# Board.net
KiCad netlist of a schematic drawn in Altium Designer
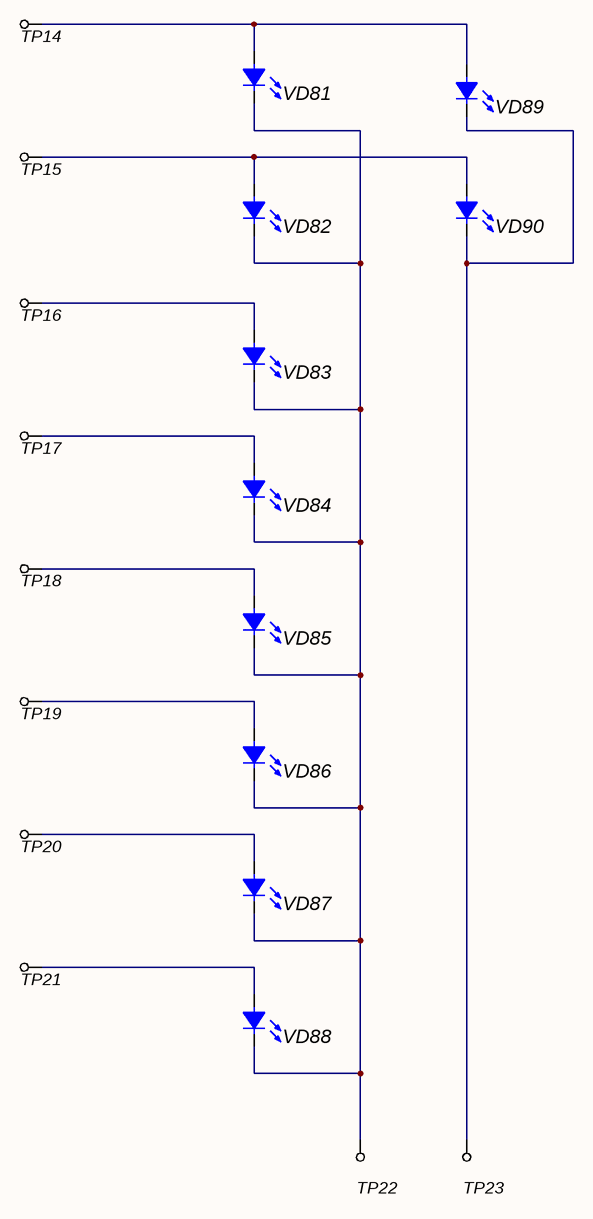
[diagram p0: Board.SchDoc]

(export (version "E")
  (design (tool "Eeschema 10.0.6"))
  (components
    (comp (ref "TP14")
      (value "Testpoint_HS1mm")
      (footprint "TestPoint(without 3D)")
      (libsource (lib "connector") (part "Testpoint_HS1mm"))
    )
    (comp (ref "TP15")
      (value "Testpoint_HS1mm")
      (footprint "TestPoint(without 3D)")
      (libsource (lib "connector") (part "Testpoint_HS1mm"))
    )
    (comp (ref "TP16")
      (value "Testpoint_HS1mm")
      (footprint "TestPoint(without 3D)")
      (libsource (lib "connector") (part "Testpoint_HS1mm"))
    )
    (comp (ref "TP17")
      (value "Testpoint_HS1mm")
      (footprint "TestPoint(without 3D)")
      (libsource (lib "connector") (part "Testpoint_HS1mm"))
    )
    (comp (ref "TP18")
      (value "Testpoint_HS1mm")
      (footprint "TestPoint(without 3D)")
      (libsource (lib "connector") (part "Testpoint_HS1mm"))
    )
    (comp (ref "TP19")
      (value "Testpoint_HS1mm")
      (footprint "TestPoint(without 3D)")
      (libsource (lib "connector") (part "Testpoint_HS1mm"))
    )
    (comp (ref "TP20")
      (value "Testpoint_HS1mm")
      (footprint "TestPoint(without 3D)")
      (libsource (lib "connector") (part "Testpoint_HS1mm"))
    )
    (comp (ref "TP21")
      (value "Testpoint_HS1mm")
      (footprint "TestPoint(without 3D)")
      (libsource (lib "connector") (part "Testpoint_HS1mm"))
    )
    (comp (ref "TP22")
      (value "Testpoint_HS1mm")
      (footprint "TestPoint(without 3D)")
      (libsource (lib "connector") (part "Testpoint_HS1mm"))
    )
    (comp (ref "TP23")
      (value "Testpoint_HS1mm")
      (footprint "TestPoint(without 3D)")
      (libsource (lib "connector") (part "Testpoint_HS1mm"))
    )
    (comp (ref "VD81")
      (value "~")
      (footprint "LED: 1206Y")
      (fields (field (name "VALUEMANUFACTURERPARTNUMBER") "LED, Green, *, *, *, -55...+150°C"))
      (libsource (lib "diode") (part "LED_single"))
    )
    (comp (ref "VD82")
      (value "~")
      (footprint "LED: 1206Y")
      (fields (field (name "VALUEMANUFACTURERPARTNUMBER") "LED, Green, *, *, *, -55...+150°C"))
      (libsource (lib "diode") (part "LED_single"))
    )
    (comp (ref "VD83")
      (value "~")
      (footprint "LED: 1206Y")
      (fields (field (name "VALUEMANUFACTURERPARTNUMBER") "LED, Green, *, *, *, -55...+150°C"))
      (libsource (lib "diode") (part "LED_single"))
    )
    (comp (ref "VD84")
      (value "~")
      (footprint "LED: 1206Y")
      (fields (field (name "VALUEMANUFACTURERPARTNUMBER") "LED, Green, *, *, *, -55...+150°C"))
      (libsource (lib "diode") (part "LED_single"))
    )
    (comp (ref "VD85")
      (value "~")
      (footprint "LED: 1206Y")
      (fields (field (name "VALUEMANUFACTURERPARTNUMBER") "LED, Green, *, *, *, -55...+150°C"))
      (libsource (lib "diode") (part "LED_single"))
    )
    (comp (ref "VD86")
      (value "~")
      (footprint "LED: 1206Y")
      (fields (field (name "VALUEMANUFACTURERPARTNUMBER") "LED, Green, *, *, *, -55...+150°C"))
      (libsource (lib "diode") (part "LED_single"))
    )
    (comp (ref "VD87")
      (value "~")
      (footprint "LED: 1206Y")
      (fields (field (name "VALUEMANUFACTURERPARTNUMBER") "LED, Green, *, *, *, -55...+150°C"))
      (libsource (lib "diode") (part "LED_single"))
    )
    (comp (ref "VD88")
      (value "~")
      (footprint "LED: 1206Y")
      (fields (field (name "VALUEMANUFACTURERPARTNUMBER") "LED, Green, *, *, *, -55...+150°C"))
      (libsource (lib "diode") (part "LED_single"))
    )
    (comp (ref "VD89")
      (value "~")
      (footprint "LED: 1206Y")
      (fields (field (name "VALUEMANUFACTURERPARTNUMBER") "LED, Green, *, *, *, -55...+150°C"))
      (libsource (lib "diode") (part "LED_single"))
    )
    (comp (ref "VD90")
      (value "~")
      (footprint "LED: 1206Y")
      (fields (field (name "VALUEMANUFACTURERPARTNUMBER") "LED, Green, *, *, *, -55...+150°C"))
      (libsource (lib "diode") (part "LED_single"))
    )
  )
  (nets
    (net (code "1") (name "Net-(VD81-A)") (class "Default")
      (node (ref "TP14") (pin "1") (pinfunction "1_1") (pintype "passive"))
      (node (ref "VD81") (pin "1") (pinfunction "A_1") (pintype "passive"))
      (node (ref "VD89") (pin "1") (pinfunction "A_1") (pintype "passive"))
    )
    (net (code "2") (name "Net-(VD81-C)") (class "Default")
      (node (ref "TP22") (pin "1") (pinfunction "1_1") (pintype "passive"))
      (node (ref "VD81") (pin "2") (pinfunction "C_2") (pintype "passive"))
      (node (ref "VD82") (pin "2") (pinfunction "C_2") (pintype "passive"))
      (node (ref "VD83") (pin "2") (pinfunction "C_2") (pintype "passive"))
      (node (ref "VD84") (pin "2") (pinfunction "C_2") (pintype "passive"))
      (node (ref "VD85") (pin "2") (pinfunction "C_2") (pintype "passive"))
      (node (ref "VD86") (pin "2") (pinfunction "C_2") (pintype "passive"))
      (node (ref "VD87") (pin "2") (pinfunction "C_2") (pintype "passive"))
      (node (ref "VD88") (pin "2") (pinfunction "C_2") (pintype "passive"))
    )
    (net (code "3") (name "Net-(VD82-A)") (class "Default")
      (node (ref "TP15") (pin "1") (pinfunction "1_1") (pintype "passive"))
      (node (ref "VD82") (pin "1") (pinfunction "A_1") (pintype "passive"))
      (node (ref "VD90") (pin "1") (pinfunction "A_1") (pintype "passive"))
    )
    (net (code "4") (name "Net-(VD83-A)") (class "Default")
      (node (ref "TP16") (pin "1") (pinfunction "1_1") (pintype "passive"))
      (node (ref "VD83") (pin "1") (pinfunction "A_1") (pintype "passive"))
    )
    (net (code "5") (name "Net-(VD84-A)") (class "Default")
      (node (ref "TP17") (pin "1") (pinfunction "1_1") (pintype "passive"))
      (node (ref "VD84") (pin "1") (pinfunction "A_1") (pintype "passive"))
    )
    (net (code "6") (name "Net-(VD85-A)") (class "Default")
      (node (ref "TP18") (pin "1") (pinfunction "1_1") (pintype "passive"))
      (node (ref "VD85") (pin "1") (pinfunction "A_1") (pintype "passive"))
    )
    (net (code "7") (name "Net-(VD86-A)") (class "Default")
      (node (ref "TP19") (pin "1") (pinfunction "1_1") (pintype "passive"))
      (node (ref "VD86") (pin "1") (pinfunction "A_1") (pintype "passive"))
    )
    (net (code "8") (name "Net-(VD87-A)") (class "Default")
      (node (ref "TP20") (pin "1") (pinfunction "1_1") (pintype "passive"))
      (node (ref "VD87") (pin "1") (pinfunction "A_1") (pintype "passive"))
    )
    (net (code "9") (name "Net-(VD88-A)") (class "Default")
      (node (ref "TP21") (pin "1") (pinfunction "1_1") (pintype "passive"))
      (node (ref "VD88") (pin "1") (pinfunction "A_1") (pintype "passive"))
    )
    (net (code "10") (name "Net-(VD89-C)") (class "Default")
      (node (ref "TP23") (pin "1") (pinfunction "1_1") (pintype "passive"))
      (node (ref "VD89") (pin "2") (pinfunction "C_2") (pintype "passive"))
      (node (ref "VD90") (pin "2") (pinfunction "C_2") (pintype "passive"))
    )
  )
)
